# sCHEMA.net
KiCad netlist of a schematic drawn in EasyEDA
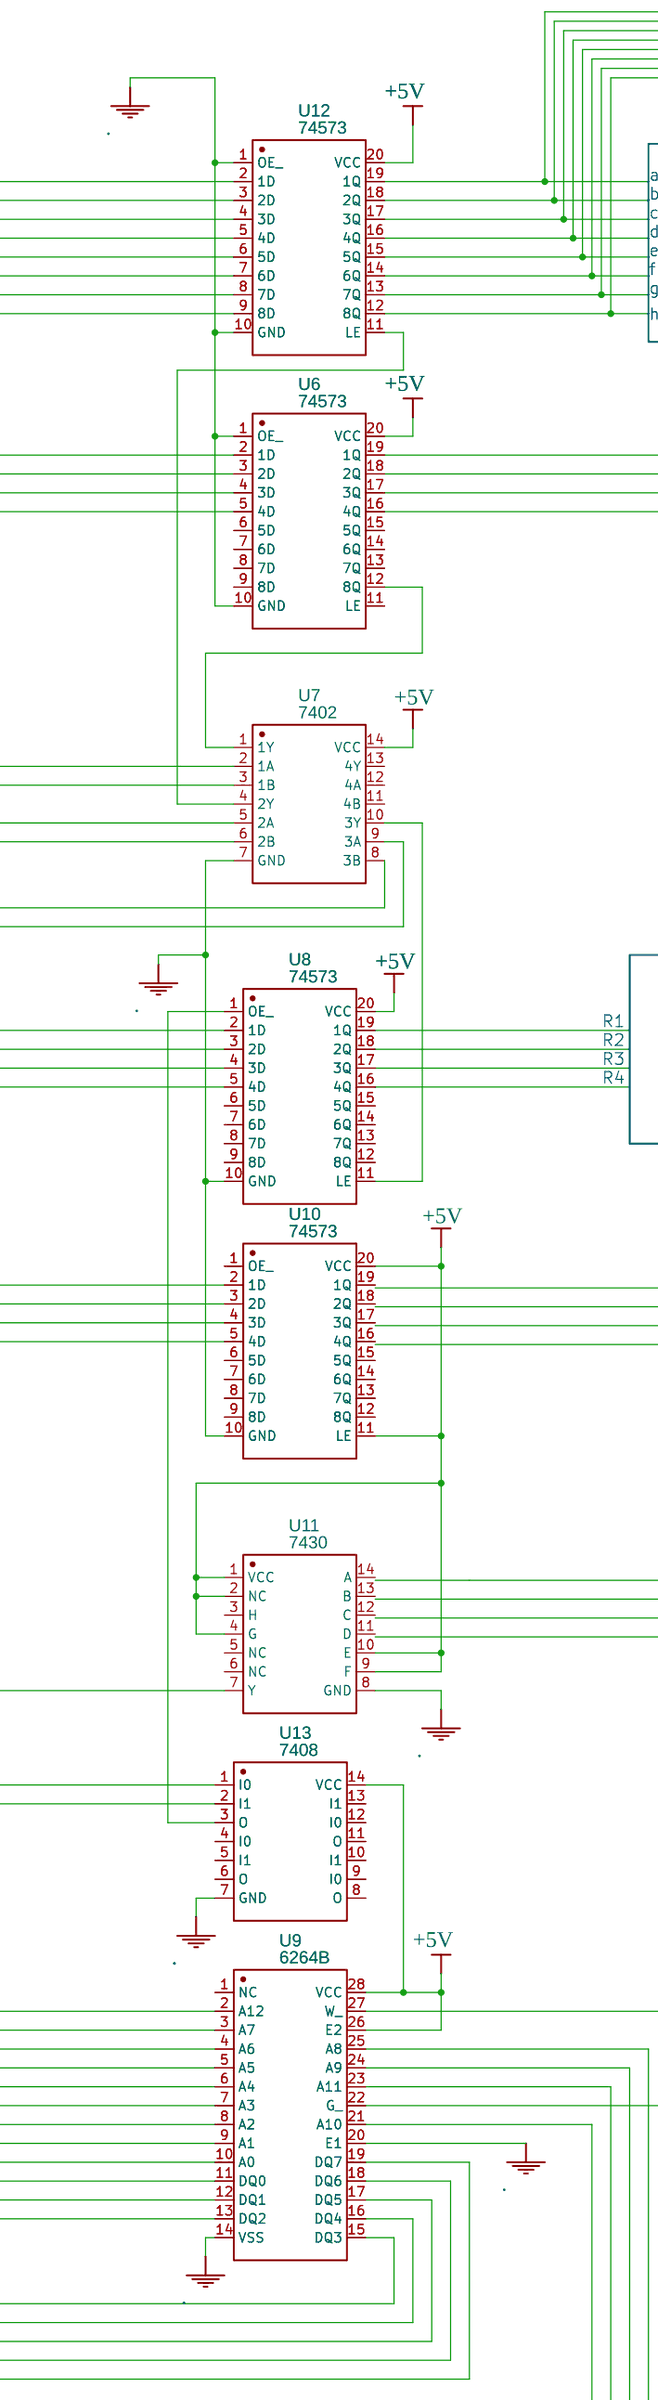
[diagram p0: schematic sheet]

(export (version "E")
  (design (tool "Eeschema 10.0.6"))
  (components
    (comp (ref "U6")
      (value "74573")
      (fields (field (name "BOM_Manufacturer Part") "?"))
      (libsource (lib "") (part "Unknown_1135_275"))
    )
    (comp (ref "U7")
      (value "7402")
      (fields (field (name "BOM_Manufacturer Part") "?"))
      (libsource (lib "") (part "Unknown_1135_425"))
    )
    (comp (ref "U8")
      (value "74573")
      (fields (field (name "BOM_Manufacturer Part") "?"))
      (libsource (lib "") (part "Unknown_1130_580"))
    )
    (comp (ref "U9")
      (value "6264B")
      (fields (field (name "BOM_Manufacturer Part") "?"))
      (libsource (lib "") (part "Unknown_1125_1120"))
    )
    (comp (ref "U10")
      (value "74573")
      (fields (field (name "BOM_Manufacturer Part") "?"))
      (libsource (lib "") (part "Unknown_1130_715"))
    )
    (comp (ref "U11")
      (value "7430")
      (fields
        (field (name "BOM_Manufacturer Part") "74HCT164D,652")
        (field (name "BOM_Supplier Part") "C5971")
      )
      (libsource (lib "") (part "Unknown_1130_865"))
    )
    (comp (ref "U12")
      (value "74573")
      (fields (field (name "BOM_Manufacturer Part") "?"))
      (libsource (lib "") (part "Unknown_1135_130"))
    )
    (comp (ref "U13")
      (value "7408")
      (fields (field (name "BOM_Manufacturer Part") "?"))
      (libsource (lib "") (part "Unknown_1125_975"))
    )
  )
  (nets
    (net (code "1") (name "+5V") (class "Default")
      (node (ref "U10") (pin "11") (pinfunction "LE_11") (pintype "unspecified"))
      (node (ref "U10") (pin "20") (pinfunction "VCC_20") (pintype "unspecified"))
      (node (ref "U11") (pin "1") (pinfunction "VCC_1") (pintype "unspecified"))
      (node (ref "U11") (pin "10") (pinfunction "E_10") (pintype "unspecified"))
      (node (ref "U11") (pin "2") (pinfunction "NC_2") (pintype "unspecified"))
      (node (ref "U11") (pin "4") (pinfunction "G_4") (pintype "unspecified"))
      (node (ref "U11") (pin "9") (pinfunction "F_9") (pintype "unspecified"))
      (node (ref "U12") (pin "20") (pinfunction "VCC_20") (pintype "unspecified"))
      (node (ref "U13") (pin "14") (pinfunction "VCC_14") (pintype "unspecified"))
      (node (ref "U6") (pin "20") (pinfunction "VCC_20") (pintype "unspecified"))
      (node (ref "U7") (pin "14") (pinfunction "VCC_14") (pintype "unspecified"))
      (node (ref "U8") (pin "20") (pinfunction "VCC_20") (pintype "unspecified"))
      (node (ref "U9") (pin "26") (pinfunction "E2_26") (pintype "unspecified"))
      (node (ref "U9") (pin "28") (pinfunction "VCC_28") (pintype "unspecified"))
    )
    (net (code "2") (name ".") (class "Default")
      (node (ref "U10") (pin "10") (pinfunction "GND_10") (pintype "unspecified"))
      (node (ref "U11") (pin "8") (pinfunction "GND_8") (pintype "unspecified"))
      (node (ref "U12") (pin "1") (pinfunction "OE__1") (pintype "unspecified"))
      (node (ref "U12") (pin "10") (pinfunction "GND_10") (pintype "unspecified"))
      (node (ref "U13") (pin "7") (pinfunction "GND_7") (pintype "unspecified"))
      (node (ref "U6") (pin "1") (pinfunction "OE__1") (pintype "unspecified"))
      (node (ref "U6") (pin "10") (pinfunction "GND_10") (pintype "unspecified"))
      (node (ref "U7") (pin "7") (pinfunction "GND_7") (pintype "unspecified"))
      (node (ref "U8") (pin "10") (pinfunction "GND_10") (pintype "unspecified"))
      (node (ref "U9") (pin "14") (pinfunction "VSS_14") (pintype "unspecified"))
      (node (ref "U9") (pin "20") (pinfunction "E1_20") (pintype "unspecified"))
    )
    (net (code "3") (name "Net-(U6-8Q)") (class "Default")
      (node (ref "U6") (pin "12") (pinfunction "8Q_12") (pintype "unspecified"))
      (node (ref "U7") (pin "1") (pinfunction "1Y_1") (pintype "unspecified"))
    )
    (net (code "4") (name "Net-(U7-1A)") (class "Default")
      (node (ref "U7") (pin "2") (pinfunction "1A_2") (pintype "unspecified"))
      (node (ref "U7") (pin "5") (pinfunction "2A_5") (pintype "unspecified"))
      (node (ref "U7") (pin "9") (pinfunction "3A_9") (pintype "unspecified"))
      (node (ref "U9") (pin "10") (pinfunction "A0_10") (pintype "unspecified"))
      (node (ref "U9") (pin "2") (pinfunction "A12_2") (pintype "unspecified"))
      (node (ref "U9") (pin "21") (pinfunction "A10_21") (pintype "unspecified"))
      (node (ref "U9") (pin "23") (pinfunction "A11_23") (pintype "unspecified"))
      (node (ref "U9") (pin "24") (pinfunction "A9_24") (pintype "unspecified"))
      (node (ref "U9") (pin "25") (pinfunction "A8_25") (pintype "unspecified"))
      (node (ref "U9") (pin "3") (pinfunction "A7_3") (pintype "unspecified"))
      (node (ref "U9") (pin "4") (pinfunction "A6_4") (pintype "unspecified"))
      (node (ref "U9") (pin "5") (pinfunction "A5_5") (pintype "unspecified"))
      (node (ref "U9") (pin "6") (pinfunction "A4_6") (pintype "unspecified"))
      (node (ref "U9") (pin "7") (pinfunction "A3_7") (pintype "unspecified"))
      (node (ref "U9") (pin "8") (pinfunction "A2_8") (pintype "unspecified"))
      (node (ref "U9") (pin "9") (pinfunction "A1_9") (pintype "unspecified"))
    )
    (net (code "5") (name "Net-(U7-1B)") (class "Default")
      (node (ref "U7") (pin "3") (pinfunction "1B_3") (pintype "unspecified"))
      (node (ref "U7") (pin "6") (pinfunction "2B_6") (pintype "unspecified"))
      (node (ref "U7") (pin "8") (pinfunction "3B_8") (pintype "unspecified"))
    )
    (net (code "6") (name "Net-(U7-3Y)") (class "Default")
      (node (ref "U7") (pin "10") (pinfunction "3Y_10") (pintype "unspecified"))
      (node (ref "U8") (pin "11") (pinfunction "LE_11") (pintype "unspecified"))
    )
    (net (code "7") (name "Net-(U8-OE_)") (class "Default")
      (node (ref "U13") (pin "3") (pinfunction "O_3") (pintype "unspecified"))
      (node (ref "U8") (pin "1") (pinfunction "OE__1") (pintype "unspecified"))
    )
    (net (code "8") (name "Net-(U10-1D)") (class "Default")
      (node (ref "U10") (pin "2") (pinfunction "1D_2") (pintype "unspecified"))
      (node (ref "U10") (pin "3") (pinfunction "2D_3") (pintype "unspecified"))
      (node (ref "U10") (pin "4") (pinfunction "3D_4") (pintype "unspecified"))
      (node (ref "U10") (pin "5") (pinfunction "4D_5") (pintype "unspecified"))
      (node (ref "U12") (pin "2") (pinfunction "1D_2") (pintype "unspecified"))
      (node (ref "U12") (pin "3") (pinfunction "2D_3") (pintype "unspecified"))
      (node (ref "U12") (pin "4") (pinfunction "3D_4") (pintype "unspecified"))
      (node (ref "U12") (pin "5") (pinfunction "4D_5") (pintype "unspecified"))
      (node (ref "U12") (pin "6") (pinfunction "5D_6") (pintype "unspecified"))
      (node (ref "U12") (pin "7") (pinfunction "6D_7") (pintype "unspecified"))
      (node (ref "U12") (pin "8") (pinfunction "7D_8") (pintype "unspecified"))
      (node (ref "U12") (pin "9") (pinfunction "8D_9") (pintype "unspecified"))
      (node (ref "U6") (pin "2") (pinfunction "1D_2") (pintype "unspecified"))
      (node (ref "U6") (pin "3") (pinfunction "2D_3") (pintype "unspecified"))
      (node (ref "U6") (pin "4") (pinfunction "3D_4") (pintype "unspecified"))
      (node (ref "U6") (pin "5") (pinfunction "4D_5") (pintype "unspecified"))
      (node (ref "U8") (pin "2") (pinfunction "1D_2") (pintype "unspecified"))
      (node (ref "U8") (pin "3") (pinfunction "2D_3") (pintype "unspecified"))
      (node (ref "U8") (pin "4") (pinfunction "3D_4") (pintype "unspecified"))
      (node (ref "U8") (pin "5") (pinfunction "4D_5") (pintype "unspecified"))
      (node (ref "U9") (pin "11") (pinfunction "DQ0_11") (pintype "unspecified"))
      (node (ref "U9") (pin "12") (pinfunction "DQ1_12") (pintype "unspecified"))
      (node (ref "U9") (pin "13") (pinfunction "DQ2_13") (pintype "unspecified"))
      (node (ref "U9") (pin "15") (pinfunction "DQ3_15") (pintype "unspecified"))
      (node (ref "U9") (pin "16") (pinfunction "DQ4_16") (pintype "unspecified"))
      (node (ref "U9") (pin "17") (pinfunction "DQ5_17") (pintype "unspecified"))
      (node (ref "U9") (pin "18") (pinfunction "DQ6_18") (pintype "unspecified"))
      (node (ref "U9") (pin "19") (pinfunction "DQ7_19") (pintype "unspecified"))
    )
    (net (code "9") (name "Net-(U12-LE)") (class "Default")
      (node (ref "U12") (pin "11") (pinfunction "LE_11") (pintype "unspecified"))
      (node (ref "U7") (pin "4") (pinfunction "2Y_4") (pintype "unspecified"))
    )
    (net (code "10") (name "unconnected-(U6-1Q-Pad19)") (class "Default")
      (node (ref "U6") (pin "19") (pinfunction "1Q_19") (pintype "unspecified"))
    )
    (net (code "11") (name "unconnected-(U6-2Q-Pad18)") (class "Default")
      (node (ref "U6") (pin "18") (pinfunction "2Q_18") (pintype "unspecified"))
    )
    (net (code "12") (name "unconnected-(U6-3Q-Pad17)") (class "Default")
      (node (ref "U6") (pin "17") (pinfunction "3Q_17") (pintype "unspecified"))
    )
    (net (code "13") (name "unconnected-(U6-4Q-Pad16)") (class "Default")
      (node (ref "U6") (pin "16") (pinfunction "4Q_16") (pintype "unspecified"))
    )
    (net (code "14") (name "unconnected-(U6-5D-Pad6)") (class "Default")
      (node (ref "U6") (pin "6") (pinfunction "5D_6") (pintype "unspecified"))
    )
    (net (code "15") (name "unconnected-(U6-5Q-Pad15)") (class "Default")
      (node (ref "U6") (pin "15") (pinfunction "5Q_15") (pintype "unspecified"))
    )
    (net (code "16") (name "unconnected-(U6-6D-Pad7)") (class "Default")
      (node (ref "U6") (pin "7") (pinfunction "6D_7") (pintype "unspecified"))
    )
    (net (code "17") (name "unconnected-(U6-6Q-Pad14)") (class "Default")
      (node (ref "U6") (pin "14") (pinfunction "6Q_14") (pintype "unspecified"))
    )
    (net (code "18") (name "unconnected-(U6-7D-Pad8)") (class "Default")
      (node (ref "U6") (pin "8") (pinfunction "7D_8") (pintype "unspecified"))
    )
    (net (code "19") (name "unconnected-(U6-7Q-Pad13)") (class "Default")
      (node (ref "U6") (pin "13") (pinfunction "7Q_13") (pintype "unspecified"))
    )
    (net (code "20") (name "unconnected-(U6-8D-Pad9)") (class "Default")
      (node (ref "U6") (pin "9") (pinfunction "8D_9") (pintype "unspecified"))
    )
    (net (code "21") (name "unconnected-(U6-LE-Pad11)") (class "Default")
      (node (ref "U6") (pin "11") (pinfunction "LE_11") (pintype "unspecified"))
    )
    (net (code "22") (name "unconnected-(U7-4A-Pad12)") (class "Default")
      (node (ref "U7") (pin "12") (pinfunction "4A_12") (pintype "unspecified"))
    )
    (net (code "23") (name "unconnected-(U7-4B-Pad11)") (class "Default")
      (node (ref "U7") (pin "11") (pinfunction "4B_11") (pintype "unspecified"))
    )
    (net (code "24") (name "unconnected-(U7-4Y-Pad13)") (class "Default")
      (node (ref "U7") (pin "13") (pinfunction "4Y_13") (pintype "unspecified"))
    )
    (net (code "25") (name "unconnected-(U8-1Q-Pad19)") (class "Default")
      (node (ref "U8") (pin "19") (pinfunction "1Q_19") (pintype "unspecified"))
    )
    (net (code "26") (name "unconnected-(U8-2Q-Pad18)") (class "Default")
      (node (ref "U8") (pin "18") (pinfunction "2Q_18") (pintype "unspecified"))
    )
    (net (code "27") (name "unconnected-(U8-3Q-Pad17)") (class "Default")
      (node (ref "U8") (pin "17") (pinfunction "3Q_17") (pintype "unspecified"))
    )
    (net (code "28") (name "unconnected-(U8-4Q-Pad16)") (class "Default")
      (node (ref "U8") (pin "16") (pinfunction "4Q_16") (pintype "unspecified"))
    )
    (net (code "29") (name "unconnected-(U8-5D-Pad6)") (class "Default")
      (node (ref "U8") (pin "6") (pinfunction "5D_6") (pintype "unspecified"))
    )
    (net (code "30") (name "unconnected-(U8-5Q-Pad15)") (class "Default")
      (node (ref "U8") (pin "15") (pinfunction "5Q_15") (pintype "unspecified"))
    )
    (net (code "31") (name "unconnected-(U8-6D-Pad7)") (class "Default")
      (node (ref "U8") (pin "7") (pinfunction "6D_7") (pintype "unspecified"))
    )
    (net (code "32") (name "unconnected-(U8-6Q-Pad14)") (class "Default")
      (node (ref "U8") (pin "14") (pinfunction "6Q_14") (pintype "unspecified"))
    )
    (net (code "33") (name "unconnected-(U8-7D-Pad8)") (class "Default")
      (node (ref "U8") (pin "8") (pinfunction "7D_8") (pintype "unspecified"))
    )
    (net (code "34") (name "unconnected-(U8-7Q-Pad13)") (class "Default")
      (node (ref "U8") (pin "13") (pinfunction "7Q_13") (pintype "unspecified"))
    )
    (net (code "35") (name "unconnected-(U8-8D-Pad9)") (class "Default")
      (node (ref "U8") (pin "9") (pinfunction "8D_9") (pintype "unspecified"))
    )
    (net (code "36") (name "unconnected-(U8-8Q-Pad12)") (class "Default")
      (node (ref "U8") (pin "12") (pinfunction "8Q_12") (pintype "unspecified"))
    )
    (net (code "37") (name "unconnected-(U9-G_-Pad22)") (class "Default")
      (node (ref "U9") (pin "22") (pinfunction "G__22") (pintype "unspecified"))
    )
    (net (code "38") (name "unconnected-(U9-NC-Pad1)") (class "Default")
      (node (ref "U9") (pin "1") (pinfunction "NC_1") (pintype "unspecified"))
    )
    (net (code "39") (name "unconnected-(U9-W_-Pad27)") (class "Default")
      (node (ref "U9") (pin "27") (pinfunction "W__27") (pintype "unspecified"))
    )
    (net (code "40") (name "unconnected-(U10-1Q-Pad19)") (class "Default")
      (node (ref "U10") (pin "19") (pinfunction "1Q_19") (pintype "unspecified"))
    )
    (net (code "41") (name "unconnected-(U10-2Q-Pad18)") (class "Default")
      (node (ref "U10") (pin "18") (pinfunction "2Q_18") (pintype "unspecified"))
    )
    (net (code "42") (name "unconnected-(U10-3Q-Pad17)") (class "Default")
      (node (ref "U10") (pin "17") (pinfunction "3Q_17") (pintype "unspecified"))
    )
    (net (code "43") (name "unconnected-(U10-4Q-Pad16)") (class "Default")
      (node (ref "U10") (pin "16") (pinfunction "4Q_16") (pintype "unspecified"))
    )
    (net (code "44") (name "unconnected-(U10-5D-Pad6)") (class "Default")
      (node (ref "U10") (pin "6") (pinfunction "5D_6") (pintype "unspecified"))
    )
    (net (code "45") (name "unconnected-(U10-5Q-Pad15)") (class "Default")
      (node (ref "U10") (pin "15") (pinfunction "5Q_15") (pintype "unspecified"))
    )
    (net (code "46") (name "unconnected-(U10-6D-Pad7)") (class "Default")
      (node (ref "U10") (pin "7") (pinfunction "6D_7") (pintype "unspecified"))
    )
    (net (code "47") (name "unconnected-(U10-6Q-Pad14)") (class "Default")
      (node (ref "U10") (pin "14") (pinfunction "6Q_14") (pintype "unspecified"))
    )
    (net (code "48") (name "unconnected-(U10-7D-Pad8)") (class "Default")
      (node (ref "U10") (pin "8") (pinfunction "7D_8") (pintype "unspecified"))
    )
    (net (code "49") (name "unconnected-(U10-7Q-Pad13)") (class "Default")
      (node (ref "U10") (pin "13") (pinfunction "7Q_13") (pintype "unspecified"))
    )
    (net (code "50") (name "unconnected-(U10-8D-Pad9)") (class "Default")
      (node (ref "U10") (pin "9") (pinfunction "8D_9") (pintype "unspecified"))
    )
    (net (code "51") (name "unconnected-(U10-8Q-Pad12)") (class "Default")
      (node (ref "U10") (pin "12") (pinfunction "8Q_12") (pintype "unspecified"))
    )
    (net (code "52") (name "unconnected-(U10-OE_-Pad1)") (class "Default")
      (node (ref "U10") (pin "1") (pinfunction "OE__1") (pintype "unspecified"))
    )
    (net (code "53") (name "unconnected-(U11-A-Pad14)") (class "Default")
      (node (ref "U11") (pin "14") (pinfunction "A_14") (pintype "unspecified"))
    )
    (net (code "54") (name "unconnected-(U11-B-Pad13)") (class "Default")
      (node (ref "U11") (pin "13") (pinfunction "B_13") (pintype "unspecified"))
    )
    (net (code "55") (name "unconnected-(U11-C-Pad12)") (class "Default")
      (node (ref "U11") (pin "12") (pinfunction "C_12") (pintype "unspecified"))
    )
    (net (code "56") (name "unconnected-(U11-D-Pad11)") (class "Default")
      (node (ref "U11") (pin "11") (pinfunction "D_11") (pintype "unspecified"))
    )
    (net (code "57") (name "unconnected-(U11-H-Pad3)") (class "Default")
      (node (ref "U11") (pin "3") (pinfunction "H_3") (pintype "unspecified"))
    )
    (net (code "58") (name "unconnected-(U11-NC-Pad5)") (class "Default")
      (node (ref "U11") (pin "5") (pinfunction "NC_5") (pintype "unspecified"))
    )
    (net (code "59") (name "unconnected-(U11-NC-Pad6)") (class "Default")
      (node (ref "U11") (pin "6") (pinfunction "NC_6") (pintype "unspecified"))
    )
    (net (code "60") (name "unconnected-(U11-Y-Pad7)") (class "Default")
      (node (ref "U11") (pin "7") (pinfunction "Y_7") (pintype "unspecified"))
    )
    (net (code "61") (name "unconnected-(U12-1Q-Pad19)") (class "Default")
      (node (ref "U12") (pin "19") (pinfunction "1Q_19") (pintype "unspecified"))
    )
    (net (code "62") (name "unconnected-(U12-2Q-Pad18)") (class "Default")
      (node (ref "U12") (pin "18") (pinfunction "2Q_18") (pintype "unspecified"))
    )
    (net (code "63") (name "unconnected-(U12-3Q-Pad17)") (class "Default")
      (node (ref "U12") (pin "17") (pinfunction "3Q_17") (pintype "unspecified"))
    )
    (net (code "64") (name "unconnected-(U12-4Q-Pad16)") (class "Default")
      (node (ref "U12") (pin "16") (pinfunction "4Q_16") (pintype "unspecified"))
    )
    (net (code "65") (name "unconnected-(U12-5Q-Pad15)") (class "Default")
      (node (ref "U12") (pin "15") (pinfunction "5Q_15") (pintype "unspecified"))
    )
    (net (code "66") (name "unconnected-(U12-6Q-Pad14)") (class "Default")
      (node (ref "U12") (pin "14") (pinfunction "6Q_14") (pintype "unspecified"))
    )
    (net (code "67") (name "unconnected-(U12-7Q-Pad13)") (class "Default")
      (node (ref "U12") (pin "13") (pinfunction "7Q_13") (pintype "unspecified"))
    )
    (net (code "68") (name "unconnected-(U12-8Q-Pad12)") (class "Default")
      (node (ref "U12") (pin "12") (pinfunction "8Q_12") (pintype "unspecified"))
    )
    (net (code "69") (name "unconnected-(U13-I0-Pad1)") (class "Default")
      (node (ref "U13") (pin "1") (pinfunction "I0_1") (pintype "unspecified"))
    )
    (net (code "70") (name "unconnected-(U13-I0-Pad4)") (class "Default")
      (node (ref "U13") (pin "4") (pinfunction "I0_4") (pintype "unspecified"))
    )
    (net (code "71") (name "unconnected-(U13-I0-Pad9)") (class "Default")
      (node (ref "U13") (pin "9") (pinfunction "I0_9") (pintype "unspecified"))
    )
    (net (code "72") (name "unconnected-(U13-I0-Pad12)") (class "Default")
      (node (ref "U13") (pin "12") (pinfunction "I0_12") (pintype "unspecified"))
    )
    (net (code "73") (name "unconnected-(U13-I1-Pad2)") (class "Default")
      (node (ref "U13") (pin "2") (pinfunction "I1_2") (pintype "unspecified"))
    )
    (net (code "74") (name "unconnected-(U13-I1-Pad5)") (class "Default")
      (node (ref "U13") (pin "5") (pinfunction "I1_5") (pintype "unspecified"))
    )
    (net (code "75") (name "unconnected-(U13-I1-Pad10)") (class "Default")
      (node (ref "U13") (pin "10") (pinfunction "I1_10") (pintype "unspecified"))
    )
    (net (code "76") (name "unconnected-(U13-I1-Pad13)") (class "Default")
      (node (ref "U13") (pin "13") (pinfunction "I1_13") (pintype "unspecified"))
    )
    (net (code "77") (name "unconnected-(U13-O-Pad6)") (class "Default")
      (node (ref "U13") (pin "6") (pinfunction "O_6") (pintype "unspecified"))
    )
    (net (code "78") (name "unconnected-(U13-O-Pad8)") (class "Default")
      (node (ref "U13") (pin "8") (pinfunction "O_8") (pintype "unspecified"))
    )
    (net (code "79") (name "unconnected-(U13-O-Pad11)") (class "Default")
      (node (ref "U13") (pin "11") (pinfunction "O_11") (pintype "unspecified"))
    )
  )
)
